# v2.net
KiCad netlist of a schematic drawn in EAGLE
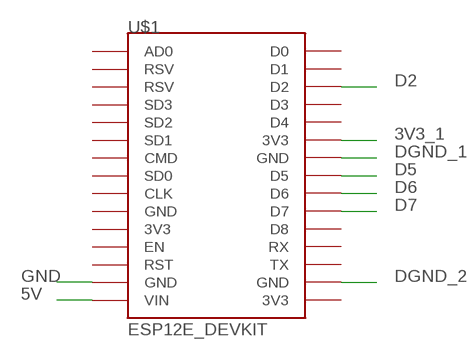
[diagram p0: schematic, sheet 1]
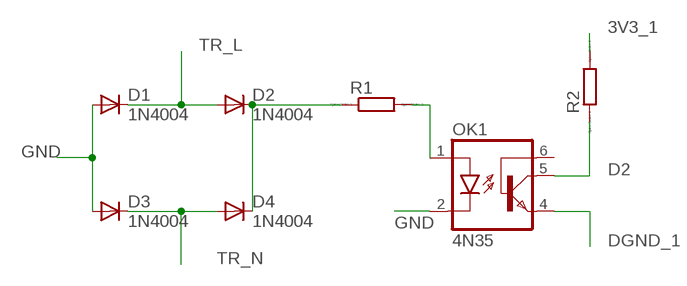
[diagram p1: schematic, sheet 2]
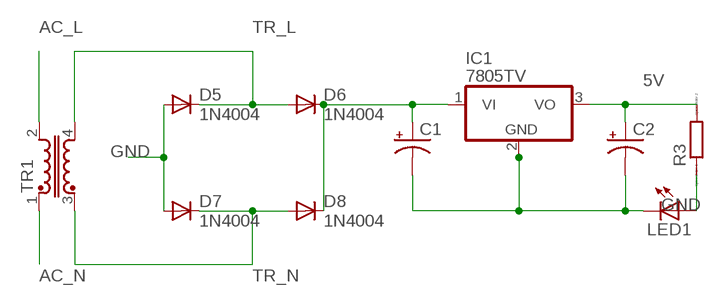
[diagram p2: schematic, sheet 3]
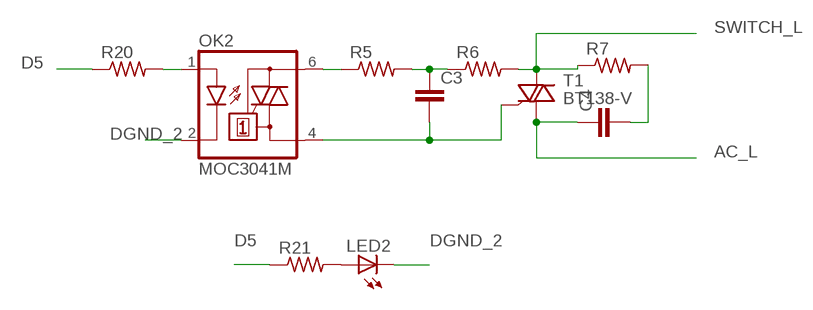
[diagram p3: schematic, sheet 4]
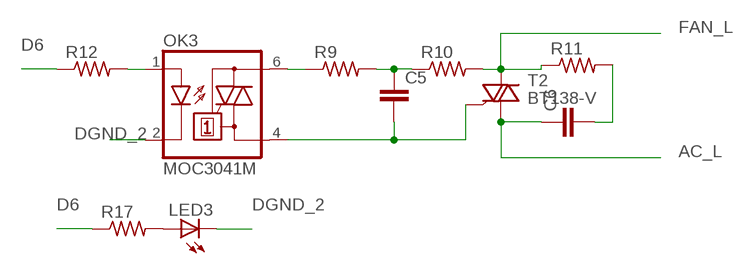
[diagram p4: schematic, sheet 5]
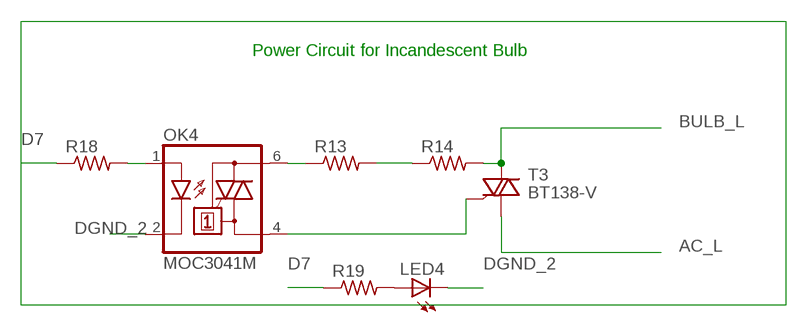
[diagram p5: schematic, sheet 6]
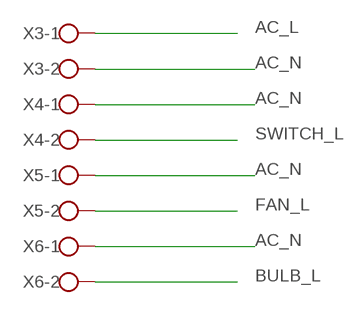
[diagram p6: schematic, sheet 7]

(export (version "E")
  (design (tool "Eeschema 10.0.6"))
  (components
    (comp (ref "C3")
      (value "C7.5/3")
      (footprint "eagle-import:C7.5B3")
      (libsource (lib "eagle-import") (part "C7.5/3"))
    )
    (comp (ref "C4")
      (value "C7.5/3")
      (footprint "eagle-import:C7.5B3")
      (libsource (lib "eagle-import") (part "C7.5/3"))
    )
    (comp (ref "LED2")
      (value "LED3MM")
      (footprint "eagle-import:LED3MM")
      (libsource (lib "eagle-import") (part "LED3MM"))
    )
    (comp (ref "OK2")
      (value "MOC3041M")
      (footprint "eagle-import:DIL06")
      (fields (field (name "MF") "FAIRCHILD SEMICONDUCTOR"))
      (libsource (lib "eagle-import") (part "MOC3041M"))
    )
    (comp (ref "R5")
      (value "R-US_0207/10")
      (footprint "eagle-import:0207_10")
      (libsource (lib "eagle-import") (part "R-US_0207/10"))
    )
    (comp (ref "R6")
      (value "R-US_0207/10")
      (footprint "eagle-import:0207_10")
      (libsource (lib "eagle-import") (part "R-US_0207/10"))
    )
    (comp (ref "R7")
      (value "R-US_0207/10")
      (footprint "eagle-import:0207_10")
      (libsource (lib "eagle-import") (part "R-US_0207/10"))
    )
    (comp (ref "R20")
      (value "R-US_0207/10")
      (footprint "eagle-import:0207_10")
      (libsource (lib "eagle-import") (part "R-US_0207/10"))
    )
    (comp (ref "R21")
      (value "R-US_0207/10")
      (footprint "eagle-import:0207_10")
      (libsource (lib "eagle-import") (part "R-US_0207/10"))
    )
    (comp (ref "T1")
      (value "BT138-V")
      (footprint "eagle-import:TO220BV")
      (libsource (lib "eagle-import") (part "BT138-V"))
    )
    (comp (ref "LED4")
      (value "LED3MM")
      (footprint "eagle-import:LED3MM")
      (libsource (lib "eagle-import") (part "LED3MM"))
    )
    (comp (ref "OK4")
      (value "MOC3041M")
      (footprint "eagle-import:DIL06")
      (fields (field (name "MF") "FAIRCHILD SEMICONDUCTOR"))
      (libsource (lib "eagle-import") (part "MOC3041M"))
    )
    (comp (ref "R13")
      (value "R-US_0207/10")
      (footprint "eagle-import:0207_10")
      (libsource (lib "eagle-import") (part "R-US_0207/10"))
    )
    (comp (ref "R14")
      (value "R-US_0207/10")
      (footprint "eagle-import:0207_10")
      (libsource (lib "eagle-import") (part "R-US_0207/10"))
    )
    (comp (ref "R18")
      (value "R-US_0207/10")
      (footprint "eagle-import:0207_10")
      (libsource (lib "eagle-import") (part "R-US_0207/10"))
    )
    (comp (ref "R19")
      (value "R-US_0207/10")
      (footprint "eagle-import:0207_10")
      (libsource (lib "eagle-import") (part "R-US_0207/10"))
    )
    (comp (ref "T3")
      (value "BT138-V")
      (footprint "eagle-import:TO220BV")
      (libsource (lib "eagle-import") (part "BT138-V"))
    )
    (comp (ref "C1")
      (value "CPOL-USE5-13")
      (footprint "eagle-import:E5-13")
      (libsource (lib "eagle-import") (part "CPOL-USE5-13"))
    )
    (comp (ref "C2")
      (value "CPOL-USE5-13")
      (footprint "eagle-import:E5-13")
      (libsource (lib "eagle-import") (part "CPOL-USE5-13"))
    )
    (comp (ref "D5")
      (value "1N4004")
      (footprint "eagle-import:DO41-10")
      (libsource (lib "eagle-import") (part "1N4004"))
    )
    (comp (ref "D6")
      (value "1N4004")
      (footprint "eagle-import:DO41-10")
      (libsource (lib "eagle-import") (part "1N4004"))
    )
    (comp (ref "D7")
      (value "1N4004")
      (footprint "eagle-import:DO41-10")
      (libsource (lib "eagle-import") (part "1N4004"))
    )
    (comp (ref "D8")
      (value "1N4004")
      (footprint "eagle-import:DO41-10")
      (libsource (lib "eagle-import") (part "1N4004"))
    )
    (comp (ref "IC1")
      (value "7805TV")
      (footprint "eagle-import:TO220V")
      (libsource (lib "eagle-import") (part "78TV05"))
    )
    (comp (ref "LED1")
      (value "LED3MM")
      (footprint "eagle-import:LED3MM")
      (libsource (lib "eagle-import") (part "LED3MM"))
    )
    (comp (ref "R3")
      (value "R0204/7")
      (footprint "eagle-import:0204_7")
      (libsource (lib "eagle-import") (part "R0204/7"))
    )
    (comp (ref "TR1")
      (value "U15-TRANSFORMER")
      (footprint "eagle-import:U15")
      (libsource (lib "eagle-import") (part "U15-TRANSFORMER"))
    )
    (comp (ref "U$1")
      (value "ESP12E_DEVKIT")
      (footprint "eagle-import:ESP12E_DEVKIT")
      (libsource (lib "eagle-import") (part "ESP12E_DEVKIT"))
    )
    (comp (ref "D1")
      (value "1N4004")
      (footprint "eagle-import:DO41-10")
      (libsource (lib "eagle-import") (part "1N4004"))
    )
    (comp (ref "D2")
      (value "1N4004")
      (footprint "eagle-import:DO41-10")
      (libsource (lib "eagle-import") (part "1N4004"))
    )
    (comp (ref "D3")
      (value "1N4004")
      (footprint "eagle-import:DO41-10")
      (libsource (lib "eagle-import") (part "1N4004"))
    )
    (comp (ref "D4")
      (value "1N4004")
      (footprint "eagle-import:DO41-10")
      (libsource (lib "eagle-import") (part "1N4004"))
    )
    (comp (ref "OK1")
      (value "4N35")
      (footprint "eagle-import:DIL06")
      (fields (field (name "MF") "FAIRCHILD SEMICONDUCTOR"))
      (libsource (lib "eagle-import") (part "4N35"))
    )
    (comp (ref "R1")
      (value "R0204/7")
      (footprint "eagle-import:0204_7")
      (libsource (lib "eagle-import") (part "R0204/7"))
    )
    (comp (ref "R2")
      (value "R0204/7")
      (footprint "eagle-import:0204_7")
      (libsource (lib "eagle-import") (part "R0204/7"))
    )
    (comp (ref "C5")
      (value "C7.5/3")
      (footprint "eagle-import:C7.5B3")
      (libsource (lib "eagle-import") (part "C7.5/3"))
    )
    (comp (ref "C6")
      (value "C7.5/3")
      (footprint "eagle-import:C7.5B3")
      (libsource (lib "eagle-import") (part "C7.5/3"))
    )
    (comp (ref "LED3")
      (value "LED3MM")
      (footprint "eagle-import:LED3MM")
      (libsource (lib "eagle-import") (part "LED3MM"))
    )
    (comp (ref "OK3")
      (value "MOC3041M")
      (footprint "eagle-import:DIL06")
      (fields (field (name "MF") "FAIRCHILD SEMICONDUCTOR"))
      (libsource (lib "eagle-import") (part "MOC3041M"))
    )
    (comp (ref "R9")
      (value "R-US_0207/10")
      (footprint "eagle-import:0207_10")
      (libsource (lib "eagle-import") (part "R-US_0207/10"))
    )
    (comp (ref "R10")
      (value "R-US_0207/10")
      (footprint "eagle-import:0207_10")
      (libsource (lib "eagle-import") (part "R-US_0207/10"))
    )
    (comp (ref "R11")
      (value "R-US_0207/10")
      (footprint "eagle-import:0207_10")
      (libsource (lib "eagle-import") (part "R-US_0207/10"))
    )
    (comp (ref "R12")
      (value "R-US_0207/10")
      (footprint "eagle-import:0207_10")
      (libsource (lib "eagle-import") (part "R-US_0207/10"))
    )
    (comp (ref "R17")
      (value "R-US_0207/10")
      (footprint "eagle-import:0207_10")
      (libsource (lib "eagle-import") (part "R-US_0207/10"))
    )
    (comp (ref "T2")
      (value "BT138-V")
      (footprint "eagle-import:TO220BV")
      (libsource (lib "eagle-import") (part "BT138-V"))
    )
    (comp (ref "X3")
      (value "W237-102")
      (footprint "eagle-import:W237-102")
      (fields (field (name "MPN") "237-102"))
      (libsource (lib "eagle-import") (part "W237-102"))
    )
    (comp (ref "X4")
      (value "W237-102")
      (footprint "eagle-import:W237-102")
      (fields (field (name "MPN") "237-102"))
      (libsource (lib "eagle-import") (part "W237-102"))
    )
    (comp (ref "X5")
      (value "W237-102")
      (footprint "eagle-import:W237-102")
      (fields (field (name "MPN") "237-102"))
      (libsource (lib "eagle-import") (part "W237-102"))
    )
    (comp (ref "X6")
      (value "W237-102")
      (footprint "eagle-import:W237-102")
      (fields (field (name "MPN") "237-102"))
      (libsource (lib "eagle-import") (part "W237-102"))
    )
  )
  (nets
    (net (code "1") (name "3V3_1") (class "Default")
      (node (ref "R2") (pin "2") (pinfunction "2_2") (pintype "passive"))
      (node (ref "U$1") (pin "3V3@1") (pinfunction "3V3_3V3@1") (pintype "bidirectional"))
    )
    (net (code "2") (name "5V") (class "Default")
      (node (ref "C2") (pin "+") (pinfunction "+_+") (pintype "passive"))
      (node (ref "IC1") (pin "3") (pinfunction "VO_3") (pintype "passive"))
      (node (ref "R3") (pin "2") (pinfunction "2_2") (pintype "passive"))
      (node (ref "U$1") (pin "VIN") (pinfunction "VIN_VIN") (pintype "bidirectional"))
    )
    (net (code "3") (name "AC_L") (class "Default")
      (node (ref "C4") (pin "1") (pinfunction "1_1") (pintype "passive"))
      (node (ref "C6") (pin "1") (pinfunction "1_1") (pintype "passive"))
      (node (ref "T1") (pin "T1") (pinfunction "A1_T1") (pintype "passive"))
      (node (ref "T2") (pin "T1") (pinfunction "A1_T1") (pintype "passive"))
      (node (ref "T3") (pin "T1") (pinfunction "A1_T1") (pintype "passive"))
      (node (ref "TR1") (pin "2") (pinfunction "2_2") (pintype "passive"))
      (node (ref "X3") (pin "1") (pinfunction "KL_1") (pintype "passive"))
    )
    (net (code "4") (name "AC_N") (class "Default")
      (node (ref "TR1") (pin "1") (pinfunction "1_1") (pintype "passive"))
      (node (ref "X3") (pin "2") (pinfunction "KL_2") (pintype "passive"))
      (node (ref "X4") (pin "1") (pinfunction "KL_1") (pintype "passive"))
      (node (ref "X5") (pin "1") (pinfunction "KL_1") (pintype "passive"))
      (node (ref "X6") (pin "1") (pinfunction "KL_1") (pintype "passive"))
    )
    (net (code "5") (name "BULB_L") (class "Default")
      (node (ref "R14") (pin "2") (pinfunction "2_2") (pintype "passive"))
      (node (ref "T3") (pin "T2") (pinfunction "A2_T2") (pintype "passive"))
      (node (ref "X6") (pin "2") (pinfunction "KL_2") (pintype "passive"))
    )
    (net (code "6") (name "D2") (class "Default")
      (node (ref "OK1") (pin "5") (pinfunction "COL_5") (pintype "passive"))
      (node (ref "R2") (pin "1") (pinfunction "1_1") (pintype "passive"))
      (node (ref "U$1") (pin "D2") (pinfunction "D2_D2") (pintype "bidirectional"))
    )
    (net (code "7") (name "D5") (class "Default")
      (node (ref "R20") (pin "1") (pinfunction "1_1") (pintype "passive"))
      (node (ref "R21") (pin "1") (pinfunction "1_1") (pintype "passive"))
      (node (ref "U$1") (pin "D5") (pinfunction "D5_D5") (pintype "bidirectional"))
    )
    (net (code "8") (name "D6") (class "Default")
      (node (ref "R12") (pin "1") (pinfunction "1_1") (pintype "passive"))
      (node (ref "R17") (pin "1") (pinfunction "1_1") (pintype "passive"))
      (node (ref "U$1") (pin "D6") (pinfunction "D6_D6") (pintype "bidirectional"))
    )
    (net (code "9") (name "D7") (class "Default")
      (node (ref "R18") (pin "1") (pinfunction "1_1") (pintype "passive"))
      (node (ref "R19") (pin "1") (pinfunction "1_1") (pintype "passive"))
      (node (ref "U$1") (pin "D7") (pinfunction "D7_D7") (pintype "bidirectional"))
    )
    (net (code "10") (name "DGND_1") (class "Default")
      (node (ref "OK1") (pin "4") (pinfunction "EMI_4") (pintype "passive"))
      (node (ref "U$1") (pin "GND@2") (pinfunction "GND_GND@2") (pintype "bidirectional"))
    )
    (net (code "11") (name "DGND_2") (class "Default")
      (node (ref "LED2") (pin "K") (pinfunction "C_K") (pintype "passive"))
      (node (ref "LED3") (pin "K") (pinfunction "C_K") (pintype "passive"))
      (node (ref "LED4") (pin "K") (pinfunction "C_K") (pintype "passive"))
      (node (ref "OK2") (pin "2") (pinfunction "C_2") (pintype "passive"))
      (node (ref "OK3") (pin "2") (pinfunction "C_2") (pintype "passive"))
      (node (ref "OK4") (pin "2") (pinfunction "C_2") (pintype "passive"))
      (node (ref "U$1") (pin "GND@3") (pinfunction "GND_GND@3") (pintype "bidirectional"))
    )
    (net (code "12") (name "FAN_L") (class "Default")
      (node (ref "R10") (pin "2") (pinfunction "2_2") (pintype "passive"))
      (node (ref "R11") (pin "1") (pinfunction "1_1") (pintype "passive"))
      (node (ref "T2") (pin "T2") (pinfunction "A2_T2") (pintype "passive"))
      (node (ref "X5") (pin "2") (pinfunction "KL_2") (pintype "passive"))
    )
    (net (code "13") (name "GND") (class "Default")
      (node (ref "C1") (pin "-") (pinfunction "-_-") (pintype "passive"))
      (node (ref "C2") (pin "-") (pinfunction "-_-") (pintype "passive"))
      (node (ref "D1") (pin "A") (pinfunction "A_A") (pintype "passive"))
      (node (ref "D3") (pin "A") (pinfunction "A_A") (pintype "passive"))
      (node (ref "D5") (pin "A") (pinfunction "A_A") (pintype "passive"))
      (node (ref "D7") (pin "A") (pinfunction "A_A") (pintype "passive"))
      (node (ref "IC1") (pin "2") (pinfunction "GND_2") (pintype "passive"))
      (node (ref "LED1") (pin "K") (pinfunction "C_K") (pintype "passive"))
      (node (ref "OK1") (pin "2") (pinfunction "C_2") (pintype "passive"))
      (node (ref "U$1") (pin "GND@1") (pinfunction "GND_GND@1") (pintype "bidirectional"))
    )
    (net (code "14") (name "Net-(C3-Pad1)") (class "Default")
      (node (ref "C3") (pin "1") (pinfunction "1_1") (pintype "passive"))
      (node (ref "R5") (pin "2") (pinfunction "2_2") (pintype "passive"))
      (node (ref "R6") (pin "1") (pinfunction "1_1") (pintype "passive"))
    )
    (net (code "15") (name "Net-(C4-Pad2)") (class "Default")
      (node (ref "C4") (pin "2") (pinfunction "2_2") (pintype "passive"))
      (node (ref "R7") (pin "2") (pinfunction "2_2") (pintype "passive"))
    )
    (net (code "16") (name "Net-(C5-Pad1)") (class "Default")
      (node (ref "C5") (pin "1") (pinfunction "1_1") (pintype "passive"))
      (node (ref "R10") (pin "1") (pinfunction "1_1") (pintype "passive"))
      (node (ref "R9") (pin "2") (pinfunction "2_2") (pintype "passive"))
    )
    (net (code "17") (name "Net-(C6-Pad2)") (class "Default")
      (node (ref "C6") (pin "2") (pinfunction "2_2") (pintype "passive"))
      (node (ref "R11") (pin "2") (pinfunction "2_2") (pintype "passive"))
    )
    (net (code "18") (name "Net-(D2-PadC)") (class "Default")
      (node (ref "D2") (pin "C") (pinfunction "C_C") (pintype "passive"))
      (node (ref "D4") (pin "C") (pinfunction "C_C") (pintype "passive"))
      (node (ref "R1") (pin "1") (pinfunction "1_1") (pintype "passive"))
    )
    (net (code "19") (name "Net-(IC1-VI)") (class "Default")
      (node (ref "C1") (pin "+") (pinfunction "+_+") (pintype "passive"))
      (node (ref "D6") (pin "C") (pinfunction "C_C") (pintype "passive"))
      (node (ref "D8") (pin "C") (pinfunction "C_C") (pintype "passive"))
      (node (ref "IC1") (pin "1") (pinfunction "VI_1") (pintype "input"))
    )
    (net (code "20") (name "Net-(LED1-PadA)") (class "Default")
      (node (ref "LED1") (pin "A") (pinfunction "A_A") (pintype "passive"))
      (node (ref "R3") (pin "1") (pinfunction "1_1") (pintype "passive"))
    )
    (net (code "21") (name "Net-(LED2-PadA)") (class "Default")
      (node (ref "LED2") (pin "A") (pinfunction "A_A") (pintype "passive"))
      (node (ref "R21") (pin "2") (pinfunction "2_2") (pintype "passive"))
    )
    (net (code "22") (name "Net-(LED3-PadA)") (class "Default")
      (node (ref "LED3") (pin "A") (pinfunction "A_A") (pintype "passive"))
      (node (ref "R17") (pin "2") (pinfunction "2_2") (pintype "passive"))
    )
    (net (code "23") (name "Net-(LED4-PadA)") (class "Default")
      (node (ref "LED4") (pin "A") (pinfunction "A_A") (pintype "passive"))
      (node (ref "R19") (pin "2") (pinfunction "2_2") (pintype "passive"))
    )
    (net (code "24") (name "Net-(OK1-A)") (class "Default")
      (node (ref "OK1") (pin "1") (pinfunction "A_1") (pintype "passive"))
      (node (ref "R1") (pin "2") (pinfunction "2_2") (pintype "passive"))
    )
    (net (code "25") (name "Net-(OK2-A)") (class "Default")
      (node (ref "OK2") (pin "1") (pinfunction "A_1") (pintype "passive"))
      (node (ref "R20") (pin "2") (pinfunction "2_2") (pintype "passive"))
    )
    (net (code "26") (name "Net-(OK2-A1)") (class "Default")
      (node (ref "C3") (pin "2") (pinfunction "2_2") (pintype "passive"))
      (node (ref "OK2") (pin "4") (pinfunction "A1_4") (pintype "passive"))
      (node (ref "T1") (pin "G") (pinfunction "G_G") (pintype "passive"))
    )
    (net (code "27") (name "Net-(OK2-A2)") (class "Default")
      (node (ref "OK2") (pin "6") (pinfunction "A2_6") (pintype "passive"))
      (node (ref "R5") (pin "1") (pinfunction "1_1") (pintype "passive"))
    )
    (net (code "28") (name "Net-(OK3-A)") (class "Default")
      (node (ref "OK3") (pin "1") (pinfunction "A_1") (pintype "passive"))
      (node (ref "R12") (pin "2") (pinfunction "2_2") (pintype "passive"))
    )
    (net (code "29") (name "Net-(OK3-A1)") (class "Default")
      (node (ref "C5") (pin "2") (pinfunction "2_2") (pintype "passive"))
      (node (ref "OK3") (pin "4") (pinfunction "A1_4") (pintype "passive"))
      (node (ref "T2") (pin "G") (pinfunction "G_G") (pintype "passive"))
    )
    (net (code "30") (name "Net-(OK3-A2)") (class "Default")
      (node (ref "OK3") (pin "6") (pinfunction "A2_6") (pintype "passive"))
      (node (ref "R9") (pin "1") (pinfunction "1_1") (pintype "passive"))
    )
    (net (code "31") (name "Net-(OK4-A)") (class "Default")
      (node (ref "OK4") (pin "1") (pinfunction "A_1") (pintype "passive"))
      (node (ref "R18") (pin "2") (pinfunction "2_2") (pintype "passive"))
    )
    (net (code "32") (name "Net-(OK4-A1)") (class "Default")
      (node (ref "OK4") (pin "4") (pinfunction "A1_4") (pintype "passive"))
      (node (ref "T3") (pin "G") (pinfunction "G_G") (pintype "passive"))
    )
    (net (code "33") (name "Net-(OK4-A2)") (class "Default")
      (node (ref "OK4") (pin "6") (pinfunction "A2_6") (pintype "passive"))
      (node (ref "R13") (pin "1") (pinfunction "1_1") (pintype "passive"))
    )
    (net (code "34") (name "Net-(R13-Pad2)") (class "Default")
      (node (ref "R13") (pin "2") (pinfunction "2_2") (pintype "passive"))
      (node (ref "R14") (pin "1") (pinfunction "1_1") (pintype "passive"))
    )
    (net (code "35") (name "SWITCH_L") (class "Default")
      (node (ref "R6") (pin "2") (pinfunction "2_2") (pintype "passive"))
      (node (ref "R7") (pin "1") (pinfunction "1_1") (pintype "passive"))
      (node (ref "T1") (pin "T2") (pinfunction "A2_T2") (pintype "passive"))
      (node (ref "X4") (pin "2") (pinfunction "KL_2") (pintype "passive"))
    )
    (net (code "36") (name "TR_L") (class "Default")
      (node (ref "D1") (pin "C") (pinfunction "C_C") (pintype "passive"))
      (node (ref "D2") (pin "A") (pinfunction "A_A") (pintype "passive"))
      (node (ref "D5") (pin "C") (pinfunction "C_C") (pintype "passive"))
      (node (ref "D6") (pin "A") (pinfunction "A_A") (pintype "passive"))
      (node (ref "TR1") (pin "4") (pinfunction "4_4") (pintype "passive"))
    )
    (net (code "37") (name "TR_N") (class "Default")
      (node (ref "D3") (pin "C") (pinfunction "C_C") (pintype "passive"))
      (node (ref "D4") (pin "A") (pinfunction "A_A") (pintype "passive"))
      (node (ref "D7") (pin "C") (pinfunction "C_C") (pintype "passive"))
      (node (ref "D8") (pin "A") (pinfunction "A_A") (pintype "passive"))
      (node (ref "TR1") (pin "3") (pinfunction "3_3") (pintype "passive"))
    )
    (net (code "38") (name "unconnected-(OK1-BAS-Pad6)") (class "Default")
      (node (ref "OK1") (pin "6") (pinfunction "BAS_6") (pintype "passive"))
    )
    (net (code "39") (name "unconnected-(U$1-3V3-Pad3V3@0)") (class "Default")
      (node (ref "U$1") (pin "3V3@0") (pinfunction "3V3_3V3@0") (pintype "bidirectional"))
    )
    (net (code "40") (name "unconnected-(U$1-3V3-Pad3V3@2)") (class "Default")
      (node (ref "U$1") (pin "3V3@2") (pinfunction "3V3_3V3@2") (pintype "bidirectional"))
    )
    (net (code "41") (name "unconnected-(U$1-GND-PadGND@0)") (class "Default")
      (node (ref "U$1") (pin "GND@0") (pinfunction "GND_GND@0") (pintype "bidirectional"))
    )
    (net (code "42") (name "unconnected-(U$1-PadAD0)") (class "Default")
      (node (ref "U$1") (pin "AD0") (pinfunction "AD0_AD0") (pintype "bidirectional"))
    )
    (net (code "43") (name "unconnected-(U$1-PadCLK)") (class "Default")
      (node (ref "U$1") (pin "CLK") (pinfunction "CLK_CLK") (pintype "bidirectional"))
    )
    (net (code "44") (name "unconnected-(U$1-PadCMD)") (class "Default")
      (node (ref "U$1") (pin "CMD") (pinfunction "CMD_CMD") (pintype "bidirectional"))
    )
    (net (code "45") (name "unconnected-(U$1-PadD0)") (class "Default")
      (node (ref "U$1") (pin "D0") (pinfunction "D0_D0") (pintype "bidirectional"))
    )
    (net (code "46") (name "unconnected-(U$1-PadD1)") (class "Default")
      (node (ref "U$1") (pin "D1") (pinfunction "D1_D1") (pintype "bidirectional"))
    )
    (net (code "47") (name "unconnected-(U$1-PadD3)") (class "Default")
      (node (ref "U$1") (pin "D3") (pinfunction "D3_D3") (pintype "bidirectional"))
    )
    (net (code "48") (name "unconnected-(U$1-PadD4)") (class "Default")
      (node (ref "U$1") (pin "D4") (pinfunction "D4_D4") (pintype "bidirectional"))
    )
    (net (code "49") (name "unconnected-(U$1-PadD8)") (class "Default")
      (node (ref "U$1") (pin "D8") (pinfunction "D8_D8") (pintype "bidirectional"))
    )
    (net (code "50") (name "unconnected-(U$1-PadEN)") (class "Default")
      (node (ref "U$1") (pin "EN") (pinfunction "EN_EN") (pintype "bidirectional"))
    )
    (net (code "51") (name "unconnected-(U$1-PadRST)") (class "Default")
      (node (ref "U$1") (pin "RST") (pinfunction "RST_RST") (pintype "bidirectional"))
    )
    (net (code "52") (name "unconnected-(U$1-PadRX)") (class "Default")
      (node (ref "U$1") (pin "RX") (pinfunction "RX_RX") (pintype "bidirectional"))
    )
    (net (code "53") (name "unconnected-(U$1-PadSD0)") (class "Default")
      (node (ref "U$1") (pin "SD0") (pinfunction "SD0_SD0") (pintype "bidirectional"))
    )
    (net (code "54") (name "unconnected-(U$1-PadSD1)") (class "Default")
      (node (ref "U$1") (pin "SD1") (pinfunction "SD1_SD1") (pintype "bidirectional"))
    )
    (net (code "55") (name "unconnected-(U$1-PadSD2)") (class "Default")
      (node (ref "U$1") (pin "SD2") (pinfunction "SD2_SD2") (pintype "bidirectional"))
    )
    (net (code "56") (name "unconnected-(U$1-PadSD3)") (class "Default")
      (node (ref "U$1") (pin "SD3") (pinfunction "SD3_SD3") (pintype "bidirectional"))
    )
    (net (code "57") (name "unconnected-(U$1-PadTX)") (class "Default")
      (node (ref "U$1") (pin "TX") (pinfunction "TX_TX") (pintype "bidirectional"))
    )
    (net (code "58") (name "unconnected-(U$1-RSV-PadRSV@0)") (class "Default")
      (node (ref "U$1") (pin "RSV@0") (pinfunction "RSV_RSV@0") (pintype "bidirectional"))
    )
    (net (code "59") (name "unconnected-(U$1-RSV-PadRSV@1)") (class "Default")
      (node (ref "U$1") (pin "RSV@1") (pinfunction "RSV_RSV@1") (pintype "bidirectional"))
    )
  )
)
